# Archimedes_Thermistor_Kati.net
KiCad netlist of a schematic drawn in Altium Designer
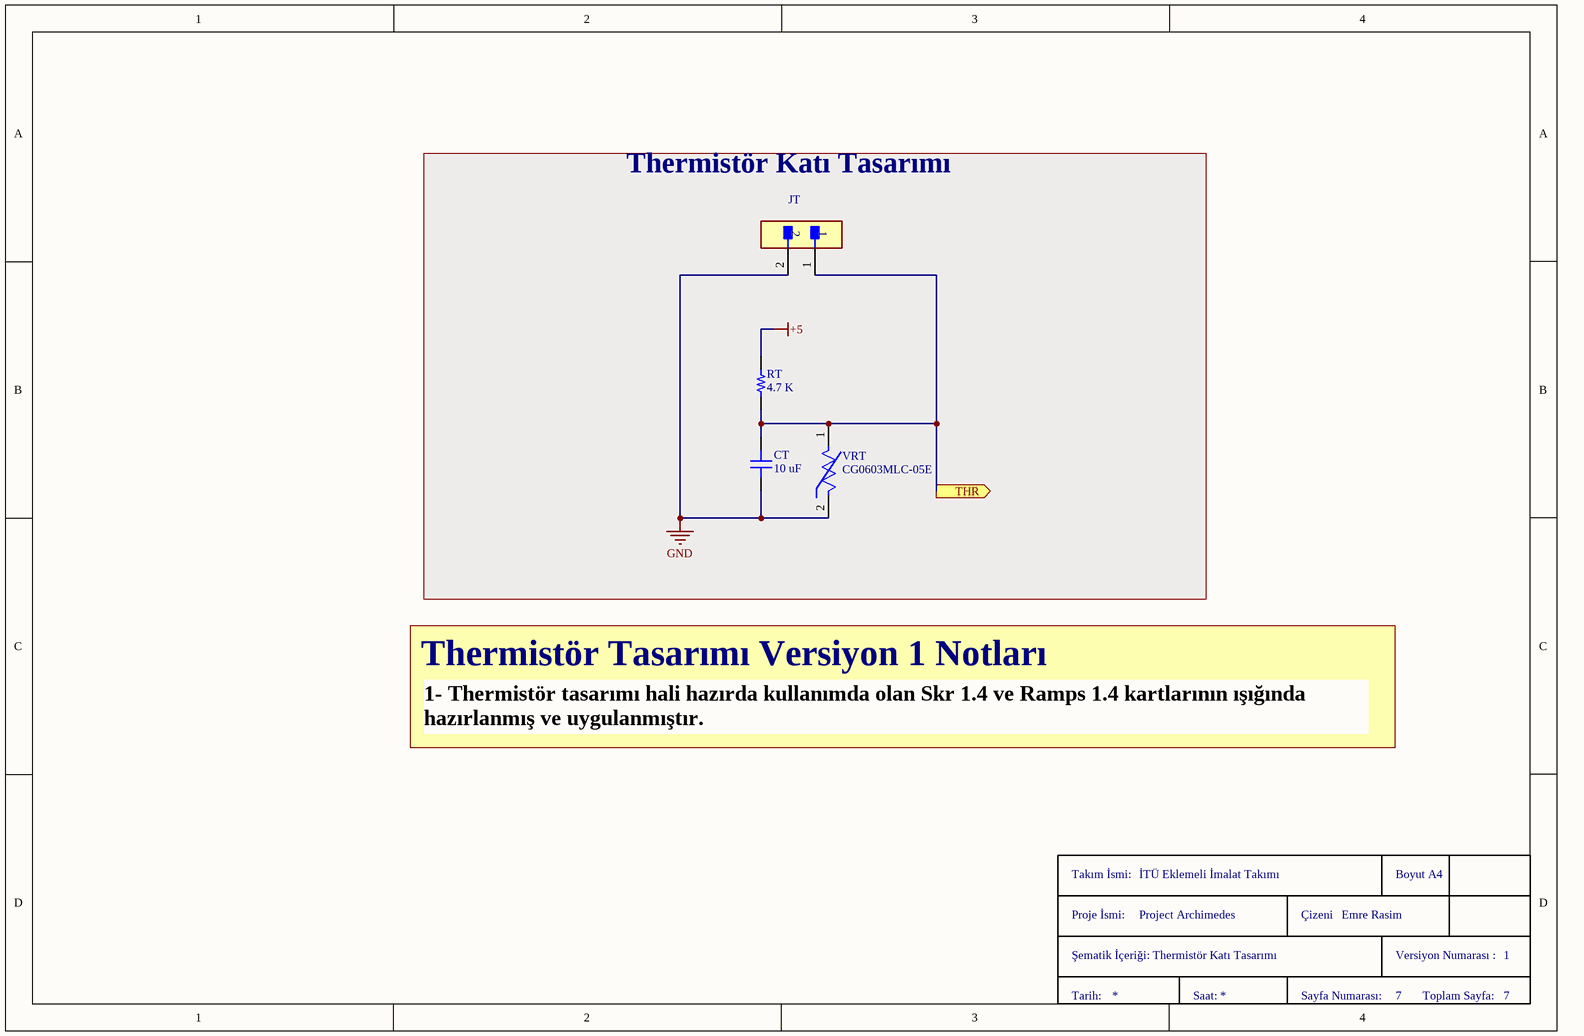
[diagram p0: Archimedes_Thermistor_Kati.SchDoc]

(export (version "E")
  (design (tool "Eeschema 10.0.6"))
  (components
    (comp (ref "CT")
      (value "10 uF")
      (footprint "CAP 1206/3216")
      (description "10 uF  and 50 Volt Ceramic Capacitor 1206 pack with X5R rating")
      (libsource (lib "Pasifler") (part "Capacitor 1206"))
    )
    (comp (ref "JT")
      (value "Con_2.5mm_2 lead_Female locked connector for 3d printer")
      (footprint "Con_2lead_2.5mm_3d_printer")
      (libsource (lib "Buck") (part "Con_2.5mm_2 lead_Female locked connector for 3d printer"))
    )
    (comp (ref "RT")
      (value "4.7 K")
      (footprint "RES 0805/2012")
      (description "4.7 K ohm Resistor  with 805 pack and %1 tolerance rating")
      (libsource (lib "Pasifler") (part "Resistor 805"))
    )
    (comp (ref "TitleBlock-A4")
      (value "TitleBlock-A4")
      (description "Title Block for İTU eklemeli imalat takımı")
      (libsource (lib "EKIM_Team_Main") (part "TitleBlock-A4"))
    )
    (comp (ref "VRT")
      (value "CG0603MLC-05E")
      (footprint "VR_Varistor_0603_CG0603MLC-05E")
      (description "Varistor with 5v voltage and 0603 package - CG0603MLC-05E")
      (libsource (lib "EKIM_Team_Main") (part "VR_0603_CG0603MLC-05E"))
    )
  )
  (nets
    (net (code "1") (name "+5") (class "Default")
      (node (ref "RT") (pin "2") (pinfunction "2_2") (pintype "passive"))
    )
    (net (code "2") (name "/THR") (class "Default")
      (node (ref "CT") (pin "2") (pinfunction "2_2") (pintype "passive"))
      (node (ref "JT") (pin "1") (pinfunction "1_1") (pintype "passive"))
      (node (ref "RT") (pin "1") (pinfunction "1_1") (pintype "passive"))
      (node (ref "VRT") (pin "1") (pinfunction "1_1") (pintype "passive"))
    )
    (net (code "3") (name "GND") (class "Default")
      (node (ref "CT") (pin "1") (pinfunction "1_1") (pintype "passive"))
      (node (ref "JT") (pin "2") (pinfunction "2_2") (pintype "passive"))
      (node (ref "VRT") (pin "2") (pinfunction "2_2") (pintype "passive"))
    )
  )
)
